# NyanTimer-v4.net
KiCad netlist of a schematic drawn in EAGLE
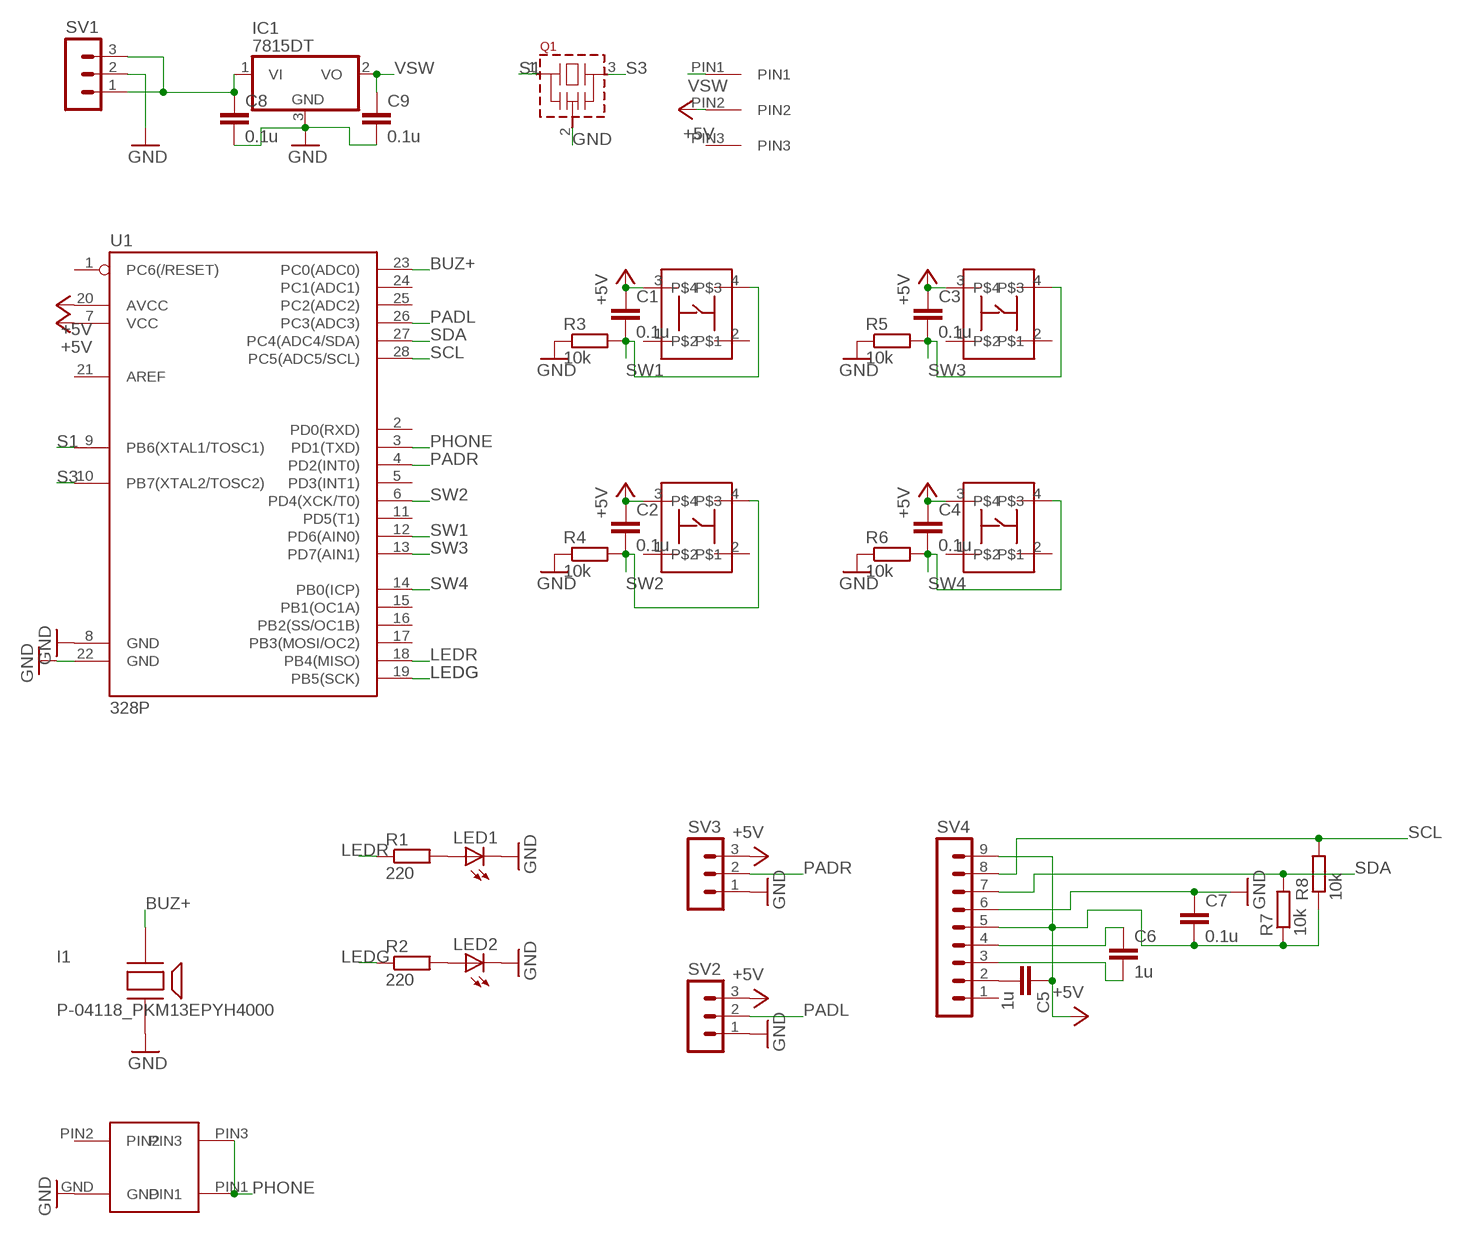
[diagram p0: schematic, sheet 1]

(export (version "E")
  (design (tool "Eeschema 10.0.6"))
  (components
    (comp (ref "C1")
      (value "0.1u")
      (footprint "eagle-import:C025-024X044")
      (libsource (lib "eagle-import") (part "C-EU025-024X044"))
    )
    (comp (ref "C2")
      (value "0.1u")
      (footprint "eagle-import:C025-024X044")
      (libsource (lib "eagle-import") (part "C-EU025-024X044"))
    )
    (comp (ref "C3")
      (value "0.1u")
      (footprint "eagle-import:C025-024X044")
      (libsource (lib "eagle-import") (part "C-EU025-024X044"))
    )
    (comp (ref "C4")
      (value "0.1u")
      (footprint "eagle-import:C025-024X044")
      (libsource (lib "eagle-import") (part "C-EU025-024X044"))
    )
    (comp (ref "C5")
      (value "1u")
      (footprint "eagle-import:C025-024X044")
      (libsource (lib "eagle-import") (part "C-EU025-024X044"))
    )
    (comp (ref "C6")
      (value "1u")
      (footprint "eagle-import:C025-024X044")
      (libsource (lib "eagle-import") (part "C-EU025-024X044"))
    )
    (comp (ref "C7")
      (value "0.1u")
      (footprint "eagle-import:C025-024X044")
      (libsource (lib "eagle-import") (part "C-EU025-024X044"))
    )
    (comp (ref "C8")
      (value "0.1u")
      (footprint "eagle-import:C025-024X044")
      (libsource (lib "eagle-import") (part "C-EU025-024X044"))
    )
    (comp (ref "C9")
      (value "0.1u")
      (footprint "eagle-import:C025-024X044")
      (libsource (lib "eagle-import") (part "C-EU025-024X044"))
    )
    (comp (ref "CONNECTOR1")
      (value "TACT_SWITCH")
      (footprint "eagle-import:TACT_SWITCH")
      (libsource (lib "eagle-import") (part "TACT_SWITCH"))
    )
    (comp (ref "CONNECTOR2")
      (value "TACT_SWITCH")
      (footprint "eagle-import:TACT_SWITCH")
      (libsource (lib "eagle-import") (part "TACT_SWITCH"))
    )
    (comp (ref "CONNECTOR3")
      (value "TACT_SWITCH")
      (footprint "eagle-import:TACT_SWITCH")
      (libsource (lib "eagle-import") (part "TACT_SWITCH"))
    )
    (comp (ref "CONNECTOR4")
      (value "TACT_SWITCH")
      (footprint "eagle-import:TACT_SWITCH")
      (libsource (lib "eagle-import") (part "TACT_SWITCH"))
    )
    (comp (ref "I1")
      (value "P-04118_PKM13EPYH4000")
      (footprint "eagle-import:PKM13EPYH4000")
      (libsource (lib "eagle-import") (part "P-04118_PKM13EPYH4000"))
    )
    (comp (ref "IC1")
      (value "7815DT")
      (footprint "eagle-import:TO252")
      (libsource (lib "eagle-import") (part "78DT15"))
    )
    (comp (ref "LED1")
      (value "LED3MM")
      (footprint "eagle-import:LED3MM")
      (libsource (lib "eagle-import") (part "LED3MM"))
    )
    (comp (ref "LED2")
      (value "LED3MM")
      (footprint "eagle-import:LED3MM")
      (libsource (lib "eagle-import") (part "LED3MM"))
    )
    (comp (ref "PHN1")
      (value "PHONE")
      (footprint "eagle-import:PHONE")
      (libsource (lib "eagle-import") (part "PHONE"))
    )
    (comp (ref "Q1")
      (value "CSTLA_T")
      (footprint "eagle-import:CSTLA_T")
      (libsource (lib "eagle-import") (part "CSTLA_T"))
    )
    (comp (ref "R1")
      (value "220")
      (footprint "eagle-import:0207_10")
      (libsource (lib "eagle-import") (part "R-EU_0207/10"))
    )
    (comp (ref "R2")
      (value "220")
      (footprint "eagle-import:0207_10")
      (libsource (lib "eagle-import") (part "R-EU_0207/10"))
    )
    (comp (ref "R3")
      (value "10k")
      (footprint "eagle-import:0207_10")
      (libsource (lib "eagle-import") (part "R-EU_0207/10"))
    )
    (comp (ref "R4")
      (value "10k")
      (footprint "eagle-import:0207_10")
      (libsource (lib "eagle-import") (part "R-EU_0207/10"))
    )
    (comp (ref "R5")
      (value "10k")
      (footprint "eagle-import:0207_10")
      (libsource (lib "eagle-import") (part "R-EU_0207/10"))
    )
    (comp (ref "R6")
      (value "10k")
      (footprint "eagle-import:0207_10")
      (libsource (lib "eagle-import") (part "R-EU_0207/10"))
    )
    (comp (ref "R7")
      (value "10k")
      (footprint "eagle-import:0207_10")
      (libsource (lib "eagle-import") (part "R-EU_0207/10"))
    )
    (comp (ref "R8")
      (value "10k")
      (footprint "eagle-import:0207_10")
      (libsource (lib "eagle-import") (part "R-EU_0207/10"))
    )
    (comp (ref "SV1")
      (value "MA03-1")
      (footprint "eagle-import:MA03-1")
      (libsource (lib "eagle-import") (part "MA03-1"))
    )
    (comp (ref "SV2")
      (value "MA03-1")
      (footprint "eagle-import:MA03-1")
      (libsource (lib "eagle-import") (part "MA03-1"))
    )
    (comp (ref "SV3")
      (value "MA03-1")
      (footprint "eagle-import:MA03-1")
      (libsource (lib "eagle-import") (part "MA03-1"))
    )
    (comp (ref "SV4")
      (value "MA09-1")
      (footprint "eagle-import:MA09-1")
      (libsource (lib "eagle-import") (part "MA09-1"))
    )
    (comp (ref "SW1")
      (value "AKIZUKI_SWITCH")
      (footprint "eagle-import:AKIZUKI_SWITCH")
      (libsource (lib "eagle-import") (part "AKIZUKI_SWITCH"))
    )
    (comp (ref "U1")
      (value "328P")
      (footprint "eagle-import:DIP28")
      (libsource (lib "eagle-import") (part "ATMEGA328P_PDIP"))
    )
  )
  (nets
    (net (code "1") (name "+5V") (class "Default")
      (node (ref "C1") (pin "1") (pinfunction "1_1") (pintype "passive"))
      (node (ref "C2") (pin "1") (pinfunction "1_1") (pintype "passive"))
      (node (ref "C3") (pin "1") (pinfunction "1_1") (pintype "passive"))
      (node (ref "C4") (pin "1") (pinfunction "1_1") (pintype "passive"))
      (node (ref "C5") (pin "1") (pinfunction "1_1") (pintype "passive"))
      (node (ref "C7") (pin "2") (pinfunction "2_2") (pintype "passive"))
      (node (ref "CONNECTOR1") (pin "3") (pinfunction "P$3_3") (pintype "bidirectional"))
      (node (ref "CONNECTOR2") (pin "3") (pinfunction "P$3_3") (pintype "bidirectional"))
      (node (ref "CONNECTOR3") (pin "3") (pinfunction "P$3_3") (pintype "bidirectional"))
      (node (ref "CONNECTOR4") (pin "3") (pinfunction "P$3_3") (pintype "bidirectional"))
      (node (ref "R7") (pin "1") (pinfunction "1_1") (pintype "passive"))
      (node (ref "R8") (pin "1") (pinfunction "1_1") (pintype "passive"))
      (node (ref "SV2") (pin "3") (pinfunction "3_3") (pintype "passive"))
      (node (ref "SV3") (pin "3") (pinfunction "3_3") (pintype "passive"))
      (node (ref "SV4") (pin "5") (pinfunction "5_5") (pintype "passive"))
      (node (ref "SV4") (pin "9") (pinfunction "9_9") (pintype "passive"))
      (node (ref "SW1") (pin "PIN2") (pinfunction "PIN2_PIN2") (pintype "bidirectional"))
      (node (ref "U1") (pin "20") (pinfunction "AVCC_20") (pintype "bidirectional"))
      (node (ref "U1") (pin "7") (pinfunction "VCC_7") (pintype "bidirectional"))
    )
    (net (code "2") (name "/BUZ+") (class "Default")
      (node (ref "I1") (pin "1") (pinfunction "1_1") (pintype "bidirectional"))
      (node (ref "U1") (pin "23") (pinfunction "PC0(ADC0)_23") (pintype "bidirectional"))
    )
    (net (code "3") (name "/LEDG") (class "Default")
      (node (ref "R2") (pin "1") (pinfunction "1_1") (pintype "passive"))
      (node (ref "U1") (pin "19") (pinfunction "PB5(SCK)_19") (pintype "bidirectional"))
    )
    (net (code "4") (name "/LEDR") (class "Default")
      (node (ref "R1") (pin "1") (pinfunction "1_1") (pintype "passive"))
      (node (ref "U1") (pin "18") (pinfunction "PB4(MISO)_18") (pintype "bidirectional"))
    )
    (net (code "5") (name "/PADL") (class "Default")
      (node (ref "SV2") (pin "2") (pinfunction "2_2") (pintype "passive"))
      (node (ref "U1") (pin "26") (pinfunction "PC3(ADC3)_26") (pintype "bidirectional"))
    )
    (net (code "6") (name "/PADR") (class "Default")
      (node (ref "SV3") (pin "2") (pinfunction "2_2") (pintype "passive"))
      (node (ref "U1") (pin "4") (pinfunction "PD2(INT0)_4") (pintype "bidirectional"))
    )
    (net (code "7") (name "/PHONE") (class "Default")
      (node (ref "PHN1") (pin "PIN1") (pinfunction "PIN1_PIN1") (pintype "bidirectional"))
      (node (ref "PHN1") (pin "PIN3") (pinfunction "PIN3_PIN3") (pintype "bidirectional"))
      (node (ref "U1") (pin "3") (pinfunction "PD1(TXD)_3") (pintype "bidirectional"))
    )
    (net (code "8") (name "/S1") (class "Default")
      (node (ref "Q1") (pin "1") (pinfunction "1_1") (pintype "output"))
      (node (ref "U1") (pin "9") (pinfunction "PB6(XTAL1/TOSC1)_9") (pintype "bidirectional"))
    )
    (net (code "9") (name "/S3") (class "Default")
      (node (ref "Q1") (pin "3") (pinfunction "3_3") (pintype "input"))
      (node (ref "U1") (pin "10") (pinfunction "PB7(XTAL2/TOSC2)_10") (pintype "bidirectional"))
    )
    (net (code "10") (name "/SCL") (class "Default")
      (node (ref "R8") (pin "2") (pinfunction "2_2") (pintype "passive"))
      (node (ref "SV4") (pin "8") (pinfunction "8_8") (pintype "passive"))
      (node (ref "U1") (pin "28") (pinfunction "PC5(ADC5/SCL)_28") (pintype "bidirectional"))
    )
    (net (code "11") (name "/SDA") (class "Default")
      (node (ref "R7") (pin "2") (pinfunction "2_2") (pintype "passive"))
      (node (ref "SV4") (pin "7") (pinfunction "7_7") (pintype "passive"))
      (node (ref "U1") (pin "27") (pinfunction "PC4(ADC4/SDA)_27") (pintype "bidirectional"))
    )
    (net (code "12") (name "/SW1") (class "Default")
      (node (ref "C1") (pin "2") (pinfunction "2_2") (pintype "passive"))
      (node (ref "CONNECTOR1") (pin "4") (pinfunction "P$4_4") (pintype "bidirectional"))
      (node (ref "R3") (pin "2") (pinfunction "2_2") (pintype "passive"))
      (node (ref "U1") (pin "12") (pinfunction "PD6(AIN0)_12") (pintype "bidirectional"))
    )
    (net (code "13") (name "/SW2") (class "Default")
      (node (ref "C2") (pin "2") (pinfunction "2_2") (pintype "passive"))
      (node (ref "CONNECTOR2") (pin "4") (pinfunction "P$4_4") (pintype "bidirectional"))
      (node (ref "R4") (pin "2") (pinfunction "2_2") (pintype "passive"))
      (node (ref "U1") (pin "6") (pinfunction "PD4(XCK/T0)_6") (pintype "bidirectional"))
    )
    (net (code "14") (name "/SW3") (class "Default")
      (node (ref "C3") (pin "2") (pinfunction "2_2") (pintype "passive"))
      (node (ref "CONNECTOR3") (pin "4") (pinfunction "P$4_4") (pintype "bidirectional"))
      (node (ref "R5") (pin "2") (pinfunction "2_2") (pintype "passive"))
      (node (ref "U1") (pin "13") (pinfunction "PD7(AIN1)_13") (pintype "bidirectional"))
    )
    (net (code "15") (name "/SW4") (class "Default")
      (node (ref "C4") (pin "2") (pinfunction "2_2") (pintype "passive"))
      (node (ref "CONNECTOR4") (pin "4") (pinfunction "P$4_4") (pintype "bidirectional"))
      (node (ref "R6") (pin "2") (pinfunction "2_2") (pintype "passive"))
      (node (ref "U1") (pin "14") (pinfunction "PB0(ICP)_14") (pintype "bidirectional"))
    )
    (net (code "16") (name "/VSW") (class "Default")
      (node (ref "C9") (pin "1") (pinfunction "1_1") (pintype "passive"))
      (node (ref "IC1") (pin "2") (pinfunction "VO_2") (pintype "passive"))
      (node (ref "SW1") (pin "PIN1") (pinfunction "PIN1_PIN1") (pintype "bidirectional"))
    )
    (net (code "17") (name "GND") (class "Default")
      (node (ref "C7") (pin "1") (pinfunction "1_1") (pintype "passive"))
      (node (ref "C8") (pin "2") (pinfunction "2_2") (pintype "passive"))
      (node (ref "C9") (pin "2") (pinfunction "2_2") (pintype "passive"))
      (node (ref "I1") (pin "2") (pinfunction "2_2") (pintype "bidirectional"))
      (node (ref "IC1") (pin "3") (pinfunction "GND_3") (pintype "passive"))
      (node (ref "LED1") (pin "K") (pinfunction "C_K") (pintype "passive"))
      (node (ref "LED2") (pin "K") (pinfunction "C_K") (pintype "passive"))
      (node (ref "PHN1") (pin "GND") (pinfunction "GND_GND") (pintype "bidirectional"))
      (node (ref "Q1") (pin "2") (pinfunction "VSS_2") (pintype "power_in"))
      (node (ref "R3") (pin "1") (pinfunction "1_1") (pintype "passive"))
      (node (ref "R4") (pin "1") (pinfunction "1_1") (pintype "passive"))
      (node (ref "R5") (pin "1") (pinfunction "1_1") (pintype "passive"))
      (node (ref "R6") (pin "1") (pinfunction "1_1") (pintype "passive"))
      (node (ref "SV1") (pin "2") (pinfunction "2_2") (pintype "passive"))
      (node (ref "SV2") (pin "1") (pinfunction "1_1") (pintype "passive"))
      (node (ref "SV3") (pin "1") (pinfunction "1_1") (pintype "passive"))
      (node (ref "SV4") (pin "6") (pinfunction "6_6") (pintype "passive"))
      (node (ref "U1") (pin "22") (pinfunction "GND_22") (pintype "bidirectional"))
      (node (ref "U1") (pin "8") (pinfunction "GND_8") (pintype "bidirectional"))
    )
    (net (code "18") (name "Net-(C5-Pad2)") (class "Default")
      (node (ref "C5") (pin "2") (pinfunction "2_2") (pintype "passive"))
      (node (ref "SV4") (pin "2") (pinfunction "2_2") (pintype "passive"))
    )
    (net (code "19") (name "Net-(C6-Pad1)") (class "Default")
      (node (ref "C6") (pin "1") (pinfunction "1_1") (pintype "passive"))
      (node (ref "SV4") (pin "4") (pinfunction "4_4") (pintype "passive"))
    )
    (net (code "20") (name "Net-(C6-Pad2)") (class "Default")
      (node (ref "C6") (pin "2") (pinfunction "2_2") (pintype "passive"))
      (node (ref "SV4") (pin "3") (pinfunction "3_3") (pintype "passive"))
    )
    (net (code "21") (name "Net-(IC1-VI)") (class "Default")
      (node (ref "C8") (pin "1") (pinfunction "1_1") (pintype "passive"))
      (node (ref "IC1") (pin "1") (pinfunction "VI_1") (pintype "input"))
      (node (ref "SV1") (pin "1") (pinfunction "1_1") (pintype "passive"))
      (node (ref "SV1") (pin "3") (pinfunction "3_3") (pintype "passive"))
    )
    (net (code "22") (name "Net-(LED1-PadA)") (class "Default")
      (node (ref "LED1") (pin "A") (pinfunction "A_A") (pintype "passive"))
      (node (ref "R1") (pin "2") (pinfunction "2_2") (pintype "passive"))
    )
    (net (code "23") (name "Net-(LED2-PadA)") (class "Default")
      (node (ref "LED2") (pin "A") (pinfunction "A_A") (pintype "passive"))
      (node (ref "R2") (pin "2") (pinfunction "2_2") (pintype "passive"))
    )
    (net (code "24") (name "unconnected-(CONNECTOR1-P$1-Pad1)") (class "Default")
      (node (ref "CONNECTOR1") (pin "1") (pinfunction "P$1_1") (pintype "bidirectional"))
    )
    (net (code "25") (name "unconnected-(CONNECTOR1-P$2-Pad2)") (class "Default")
      (node (ref "CONNECTOR1") (pin "2") (pinfunction "P$2_2") (pintype "bidirectional"))
    )
    (net (code "26") (name "unconnected-(CONNECTOR2-P$1-Pad1)") (class "Default")
      (node (ref "CONNECTOR2") (pin "1") (pinfunction "P$1_1") (pintype "bidirectional"))
    )
    (net (code "27") (name "unconnected-(CONNECTOR2-P$2-Pad2)") (class "Default")
      (node (ref "CONNECTOR2") (pin "2") (pinfunction "P$2_2") (pintype "bidirectional"))
    )
    (net (code "28") (name "unconnected-(CONNECTOR3-P$1-Pad1)") (class "Default")
      (node (ref "CONNECTOR3") (pin "1") (pinfunction "P$1_1") (pintype "bidirectional"))
    )
    (net (code "29") (name "unconnected-(CONNECTOR3-P$2-Pad2)") (class "Default")
      (node (ref "CONNECTOR3") (pin "2") (pinfunction "P$2_2") (pintype "bidirectional"))
    )
    (net (code "30") (name "unconnected-(CONNECTOR4-P$1-Pad1)") (class "Default")
      (node (ref "CONNECTOR4") (pin "1") (pinfunction "P$1_1") (pintype "bidirectional"))
    )
    (net (code "31") (name "unconnected-(CONNECTOR4-P$2-Pad2)") (class "Default")
      (node (ref "CONNECTOR4") (pin "2") (pinfunction "P$2_2") (pintype "bidirectional"))
    )
    (net (code "32") (name "unconnected-(PHN1-PadPIN2)") (class "Default")
      (node (ref "PHN1") (pin "PIN2") (pinfunction "PIN2_PIN2") (pintype "bidirectional"))
    )
    (net (code "33") (name "unconnected-(SV4-Pad1)") (class "Default")
      (node (ref "SV4") (pin "1") (pinfunction "1_1") (pintype "passive"))
    )
    (net (code "34") (name "unconnected-(SW1-PadPIN3)") (class "Default")
      (node (ref "SW1") (pin "PIN3") (pinfunction "PIN3_PIN3") (pintype "bidirectional"))
    )
    (net (code "35") (name "unconnected-(U1-AREF-Pad21)") (class "Default")
      (node (ref "U1") (pin "21") (pinfunction "AREF_21") (pintype "bidirectional"))
    )
    (net (code "36") (name "unconnected-(U1-PB1(OC1A)-Pad15)") (class "Default")
      (node (ref "U1") (pin "15") (pinfunction "PB1(OC1A)_15") (pintype "bidirectional"))
    )
    (net (code "37") (name "unconnected-(U1-PB2(SS{slash}OC1B)-Pad16)") (class "Default")
      (node (ref "U1") (pin "16") (pinfunction "PB2(SS/OC1B)_16") (pintype "bidirectional"))
    )
    (net (code "38") (name "unconnected-(U1-PB3(MOSI{slash}OC2)-Pad17)") (class "Default")
      (node (ref "U1") (pin "17") (pinfunction "PB3(MOSI/OC2)_17") (pintype "bidirectional"))
    )
    (net (code "39") (name "unconnected-(U1-PC1(ADC1)-Pad24)") (class "Default")
      (node (ref "U1") (pin "24") (pinfunction "PC1(ADC1)_24") (pintype "bidirectional"))
    )
    (net (code "40") (name "unconnected-(U1-PC2(ADC2)-Pad25)") (class "Default")
      (node (ref "U1") (pin "25") (pinfunction "PC2(ADC2)_25") (pintype "bidirectional"))
    )
    (net (code "41") (name "unconnected-(U1-PC6({slash}RESET)-Pad1)") (class "Default")
      (node (ref "U1") (pin "1") (pinfunction "PC6(/RESET)_1") (pintype "bidirectional"))
    )
    (net (code "42") (name "unconnected-(U1-PD0(RXD)-Pad2)") (class "Default")
      (node (ref "U1") (pin "2") (pinfunction "PD0(RXD)_2") (pintype "bidirectional"))
    )
    (net (code "43") (name "unconnected-(U1-PD3(INT1)-Pad5)") (class "Default")
      (node (ref "U1") (pin "5") (pinfunction "PD3(INT1)_5") (pintype "bidirectional"))
    )
    (net (code "44") (name "unconnected-(U1-PD5(T1)-Pad11)") (class "Default")
      (node (ref "U1") (pin "11") (pinfunction "PD5(T1)_11") (pintype "bidirectional"))
    )
  )
)
